# Analog_Switch_Arrays.net
KiCad netlist of a schematic drawn in Altium Designer
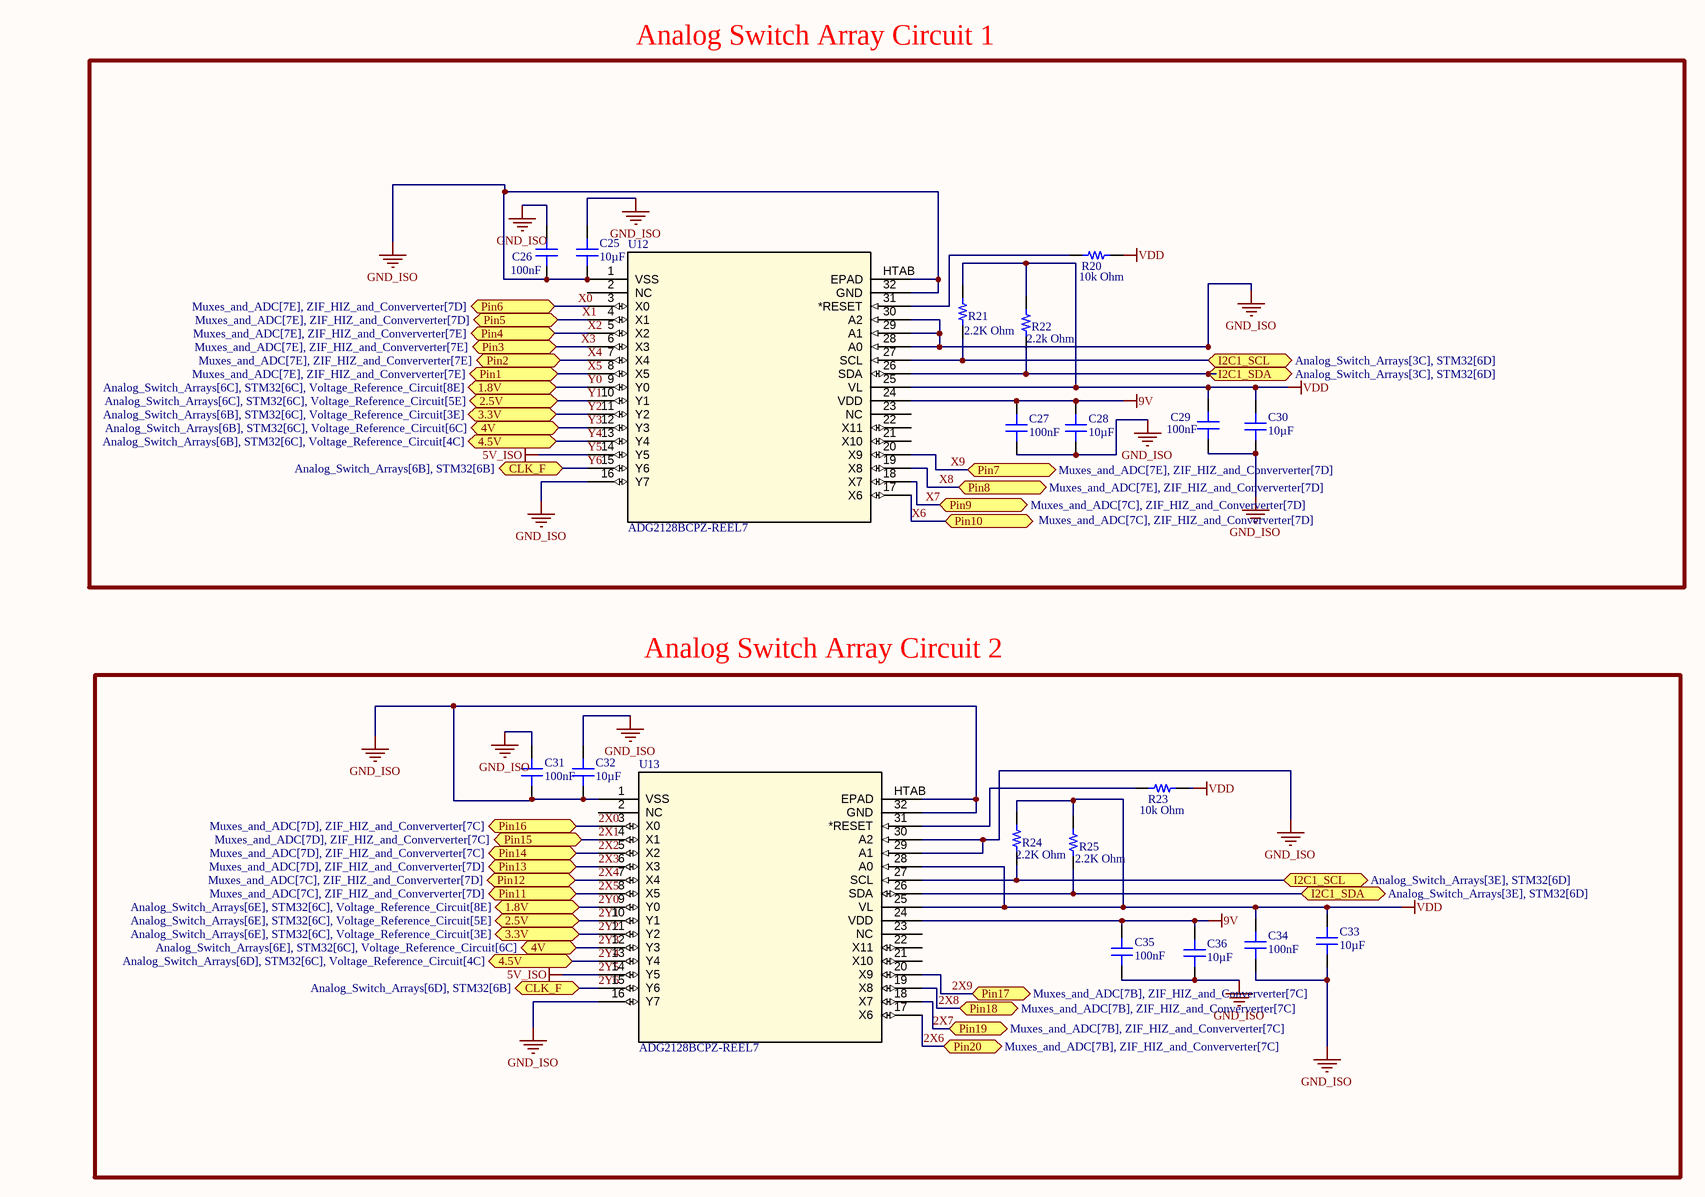
[diagram p0: Analog_Switch_Arrays.SchDoc]

(export (version "E")
  (design (tool "Eeschema 10.0.6"))
  (components
    (comp (ref "C25")
      (value "10µF")
      (footprint "MURATA CAP GCM31M 1206_3216")
      (description "CAP CER 10UF 35V X8M 1206")
      (fields (field (name "PART NUMBER") "GCM31CM8EG106KE08L"))
      (libsource (lib "University of Massachusetts Lowell") (part "CAPACITOR"))
    )
    (comp (ref "C26")
      (value "100nF")
      (footprint "CAP 1206_3216 - 0.8MM")
      (description "CAP CER 1206 0.1F 16V ULTRA STAB")
      (fields (field (name "PART NUMBER") "C1206X104G4HAC7800"))
      (libsource (lib "University of Massachusetts Lowell") (part "CAPACITOR"))
    )
    (comp (ref "C27")
      (value "100nF")
      (footprint "CAP 1206_3216 - 0.8MM")
      (description "CAP CER 1206 0.1F 16V ULTRA STAB")
      (fields (field (name "PART NUMBER") "C1206X104G4HAC7800"))
      (libsource (lib "University of Massachusetts Lowell") (part "CAPACITOR"))
    )
    (comp (ref "C28")
      (value "10µF")
      (footprint "MURATA CAP GCM31M 1206_3216")
      (description "CAP CER 10UF 35V X8M 1206")
      (fields (field (name "PART NUMBER") "GCM31CM8EG106KE08L"))
      (libsource (lib "University of Massachusetts Lowell") (part "CAPACITOR"))
    )
    (comp (ref "C29")
      (value "100nF")
      (footprint "CAP 1206_3216 - 0.8MM")
      (description "CAP CER 1206 0.1F 16V ULTRA STAB")
      (fields (field (name "PART NUMBER") "C1206X104G4HAC7800"))
      (libsource (lib "University of Massachusetts Lowell") (part "CAPACITOR"))
    )
    (comp (ref "C30")
      (value "10µF")
      (footprint "MURATA CAP GCM31M 1206_3216")
      (description "CAP CER 10UF 35V X8M 1206")
      (fields (field (name "PART NUMBER") "GCM31CM8EG106KE08L"))
      (libsource (lib "University of Massachusetts Lowell") (part "CAPACITOR"))
    )
    (comp (ref "C31")
      (value "100nF")
      (footprint "CAP 1206_3216 - 0.8MM")
      (description "CAP CER 1206 0.1F 16V ULTRA STAB")
      (fields (field (name "PART NUMBER") "C1206X104G4HAC7800"))
      (libsource (lib "University of Massachusetts Lowell") (part "CAPACITOR"))
    )
    (comp (ref "C32")
      (value "10µF")
      (footprint "MURATA CAP GCM31M 1206_3216")
      (description "CAP CER 10UF 35V X8M 1206")
      (fields (field (name "PART NUMBER") "GCM31CM8EG106KE08L"))
      (libsource (lib "University of Massachusetts Lowell") (part "CAPACITOR"))
    )
    (comp (ref "C33")
      (value "10µF")
      (footprint "MURATA CAP GCM31M 1206_3216")
      (description "CAP CER 10UF 35V X8M 1206")
      (fields (field (name "PART NUMBER") "GCM31CM8EG106KE08L"))
      (libsource (lib "University of Massachusetts Lowell") (part "CAPACITOR"))
    )
    (comp (ref "C34")
      (value "100nF")
      (footprint "CAP 1206_3216 - 0.8MM")
      (description "CAP CER 1206 0.1F 16V ULTRA STAB")
      (fields (field (name "PART NUMBER") "C1206X104G4HAC7800"))
      (libsource (lib "University of Massachusetts Lowell") (part "CAPACITOR"))
    )
    (comp (ref "C35")
      (value "100nF")
      (footprint "CAP 1206_3216 - 0.8MM")
      (description "CAP CER 1206 0.1F 16V ULTRA STAB")
      (fields (field (name "PART NUMBER") "C1206X104G4HAC7800"))
      (libsource (lib "University of Massachusetts Lowell") (part "CAPACITOR"))
    )
    (comp (ref "C36")
      (value "10µF")
      (footprint "MURATA CAP GCM31M 1206_3216")
      (description "CAP CER 10UF 35V X8M 1206")
      (fields (field (name "PART NUMBER") "GCM31CM8EG106KE08L"))
      (libsource (lib "University of Massachusetts Lowell") (part "CAPACITOR"))
    )
    (comp (ref "R20")
      (value "10k Ohm")
      (footprint "YAGEO RES 1206_3216")
      (description "RES 10K OHM 0.1% 1/4W 1206")
      (fields (field (name "PART NUMBER") "RP1206BRD0710KL"))
      (libsource (lib "University of Massachusetts Lowell") (part "RESISTOR"))
    )
    (comp (ref "R21")
      (value "2.2K Ohm")
      (footprint "RES 1210_3225")
      (description "RES 2.2K OHM 10% 1/2W 1210")
      (fields (field (name "PART NUMBER") "SG732ETTD222K"))
      (libsource (lib "University of Massachusetts Lowell") (part "RESISTOR"))
    )
    (comp (ref "R22")
      (value "2.2k Ohm")
      (footprint "RES 1210_3225")
      (description "RES 2.2K OHM 10% 1/2W 1210")
      (fields (field (name "PART NUMBER") "SG732ETTD222K"))
      (libsource (lib "University of Massachusetts Lowell") (part "RESISTOR"))
    )
    (comp (ref "R23")
      (value "10k Ohm")
      (footprint "YAGEO RES 1206_3216")
      (description "RES 10K OHM 0.1% 1/4W 1206")
      (fields (field (name "PART NUMBER") "RP1206BRD0710KL"))
      (libsource (lib "University of Massachusetts Lowell") (part "RESISTOR"))
    )
    (comp (ref "R24")
      (value "2.2K Ohm")
      (footprint "RES 1210_3225")
      (description "RES 2.2K OHM 10% 1/2W 1210")
      (fields (field (name "PART NUMBER") "SG732ETTD222K"))
      (libsource (lib "University of Massachusetts Lowell") (part "RESISTOR"))
    )
    (comp (ref "R25")
      (value "2.2K Ohm")
      (footprint "RES 1210_3225")
      (description "RES 2.2K OHM 10% 1/2W 1210")
      (fields (field (name "PART NUMBER") "SG732ETTD222K"))
      (libsource (lib "University of Massachusetts Lowell") (part "RESISTOR"))
    )
    (comp (ref "U12")
      (value "ADG2128BCPZ-REEL7")
      (footprint "CP_32_7_ADI")
      (description "I2C CMOS 8 X 12 Analog Switch Array with Dual/Single Supplies")
      (fields (field (name "COPYRIGHT") "Copyright (C) 2025 Ultra Librarian. All rights reserved."))
      (libsource (lib "University of Massachusetts Lowell") (part "ADG2128BCPZ-REEL7"))
    )
    (comp (ref "U13")
      (value "ADG2128BCPZ-REEL7")
      (footprint "CP_32_7_ADI")
      (description "I2C CMOS 8 X 12 Analog Switch Array with Dual/Single Supplies")
      (fields (field (name "COPYRIGHT") "Copyright (C) 2025 Ultra Librarian. All rights reserved."))
      (libsource (lib "University of Massachusetts Lowell") (part "ADG2128BCPZ-REEL7"))
    )
  )
  (nets
    (net (code "1") (name "/2X0") (class "Default")
      (node (ref "U13") (pin "3") (pinfunction "X0_3") (pintype "bidirectional"))
    )
    (net (code "2") (name "/2X1") (class "Default")
      (node (ref "U13") (pin "4") (pinfunction "X1_4") (pintype "bidirectional"))
    )
    (net (code "3") (name "/2X2") (class "Default")
      (node (ref "U13") (pin "5") (pinfunction "X2_5") (pintype "bidirectional"))
    )
    (net (code "4") (name "/2X3") (class "Default")
      (node (ref "U13") (pin "6") (pinfunction "X3_6") (pintype "bidirectional"))
    )
    (net (code "5") (name "/2X4") (class "Default")
      (node (ref "U13") (pin "7") (pinfunction "X4_7") (pintype "bidirectional"))
    )
    (net (code "6") (name "/2X5") (class "Default")
      (node (ref "U13") (pin "8") (pinfunction "X5_8") (pintype "bidirectional"))
    )
    (net (code "7") (name "/2X6") (class "Default")
      (node (ref "U13") (pin "17") (pinfunction "X6_17") (pintype "bidirectional"))
    )
    (net (code "8") (name "/2X7") (class "Default")
      (node (ref "U13") (pin "18") (pinfunction "X7_18") (pintype "bidirectional"))
    )
    (net (code "9") (name "/2X8") (class "Default")
      (node (ref "U13") (pin "19") (pinfunction "X8_19") (pintype "bidirectional"))
    )
    (net (code "10") (name "/2X9") (class "Default")
      (node (ref "U13") (pin "20") (pinfunction "X9_20") (pintype "bidirectional"))
    )
    (net (code "11") (name "/2Y0") (class "Default")
      (node (ref "U12") (pin "9") (pinfunction "Y0_9") (pintype "bidirectional"))
      (node (ref "U13") (pin "9") (pinfunction "Y0_9") (pintype "bidirectional"))
    )
    (net (code "12") (name "/2Y1") (class "Default")
      (node (ref "U12") (pin "10") (pinfunction "Y1_10") (pintype "bidirectional"))
      (node (ref "U13") (pin "10") (pinfunction "Y1_10") (pintype "bidirectional"))
    )
    (net (code "13") (name "/2Y2") (class "Default")
      (node (ref "U12") (pin "11") (pinfunction "Y2_11") (pintype "bidirectional"))
      (node (ref "U13") (pin "11") (pinfunction "Y2_11") (pintype "bidirectional"))
    )
    (net (code "14") (name "/2Y3") (class "Default")
      (node (ref "U12") (pin "12") (pinfunction "Y3_12") (pintype "bidirectional"))
      (node (ref "U13") (pin "12") (pinfunction "Y3_12") (pintype "bidirectional"))
    )
    (net (code "15") (name "/2Y4") (class "Default")
      (node (ref "U12") (pin "13") (pinfunction "Y4_13") (pintype "bidirectional"))
      (node (ref "U13") (pin "13") (pinfunction "Y4_13") (pintype "bidirectional"))
    )
    (net (code "16") (name "/2Y6") (class "Default")
      (node (ref "U12") (pin "15") (pinfunction "Y6_15") (pintype "bidirectional"))
      (node (ref "U13") (pin "15") (pinfunction "Y6_15") (pintype "bidirectional"))
    )
    (net (code "17") (name "/I2C1_SCL") (class "Default")
      (node (ref "R21") (pin "1") (pinfunction "1_1") (pintype "passive"))
      (node (ref "R24") (pin "1") (pinfunction "1_1") (pintype "passive"))
      (node (ref "U12") (pin "27") (pinfunction "SCL_27") (pintype "input"))
      (node (ref "U13") (pin "27") (pinfunction "SCL_27") (pintype "input"))
    )
    (net (code "18") (name "/I2C1_SDA") (class "Default")
      (node (ref "R22") (pin "1") (pinfunction "1_1") (pintype "passive"))
      (node (ref "R25") (pin "1") (pinfunction "1_1") (pintype "passive"))
      (node (ref "U12") (pin "26") (pinfunction "SDA_26") (pintype "bidirectional"))
      (node (ref "U13") (pin "26") (pinfunction "SDA_26") (pintype "bidirectional"))
    )
    (net (code "19") (name "/X0") (class "Default")
      (node (ref "U12") (pin "3") (pinfunction "X0_3") (pintype "bidirectional"))
    )
    (net (code "20") (name "/X1") (class "Default")
      (node (ref "U12") (pin "4") (pinfunction "X1_4") (pintype "bidirectional"))
    )
    (net (code "21") (name "/X2") (class "Default")
      (node (ref "U12") (pin "5") (pinfunction "X2_5") (pintype "bidirectional"))
    )
    (net (code "22") (name "/X3") (class "Default")
      (node (ref "U12") (pin "6") (pinfunction "X3_6") (pintype "bidirectional"))
    )
    (net (code "23") (name "/X4") (class "Default")
      (node (ref "U12") (pin "7") (pinfunction "X4_7") (pintype "bidirectional"))
    )
    (net (code "24") (name "/X5") (class "Default")
      (node (ref "U12") (pin "8") (pinfunction "X5_8") (pintype "bidirectional"))
    )
    (net (code "25") (name "/X6") (class "Default")
      (node (ref "U12") (pin "17") (pinfunction "X6_17") (pintype "bidirectional"))
    )
    (net (code "26") (name "/X7") (class "Default")
      (node (ref "U12") (pin "18") (pinfunction "X7_18") (pintype "bidirectional"))
    )
    (net (code "27") (name "/X8") (class "Default")
      (node (ref "U12") (pin "19") (pinfunction "X8_19") (pintype "bidirectional"))
    )
    (net (code "28") (name "/X9") (class "Default")
      (node (ref "U12") (pin "20") (pinfunction "X9_20") (pintype "bidirectional"))
    )
    (net (code "29") (name "5V_ISO") (class "Default")
      (node (ref "U12") (pin "14") (pinfunction "Y5_14") (pintype "bidirectional"))
      (node (ref "U13") (pin "14") (pinfunction "Y5_14") (pintype "bidirectional"))
    )
    (net (code "30") (name "9V") (class "Default")
      (node (ref "C27") (pin "2") (pinfunction "2_2") (pintype "passive"))
      (node (ref "C28") (pin "2") (pinfunction "2_2") (pintype "passive"))
      (node (ref "C35") (pin "2") (pinfunction "2_2") (pintype "passive"))
      (node (ref "C36") (pin "2") (pinfunction "2_2") (pintype "passive"))
      (node (ref "U12") (pin "24") (pinfunction "VDD_24") (pintype "power_in"))
      (node (ref "U13") (pin "24") (pinfunction "VDD_24") (pintype "power_in"))
    )
    (net (code "31") (name "GND_ISO") (class "Default")
      (node (ref "C25") (pin "1") (pinfunction "1_1") (pintype "passive"))
      (node (ref "C25") (pin "2") (pinfunction "2_2") (pintype "passive"))
      (node (ref "C26") (pin "1") (pinfunction "1_1") (pintype "passive"))
      (node (ref "C26") (pin "2") (pinfunction "2_2") (pintype "passive"))
      (node (ref "C27") (pin "1") (pinfunction "1_1") (pintype "passive"))
      (node (ref "C28") (pin "1") (pinfunction "1_1") (pintype "passive"))
      (node (ref "C29") (pin "1") (pinfunction "1_1") (pintype "passive"))
      (node (ref "C30") (pin "1") (pinfunction "1_1") (pintype "passive"))
      (node (ref "C31") (pin "1") (pinfunction "1_1") (pintype "passive"))
      (node (ref "C31") (pin "2") (pinfunction "2_2") (pintype "passive"))
      (node (ref "C32") (pin "1") (pinfunction "1_1") (pintype "passive"))
      (node (ref "C32") (pin "2") (pinfunction "2_2") (pintype "passive"))
      (node (ref "C33") (pin "1") (pinfunction "1_1") (pintype "passive"))
      (node (ref "C34") (pin "1") (pinfunction "1_1") (pintype "passive"))
      (node (ref "C35") (pin "1") (pinfunction "1_1") (pintype "passive"))
      (node (ref "C36") (pin "1") (pinfunction "1_1") (pintype "passive"))
      (node (ref "U12") (pin "1") (pinfunction "VSS_1") (pintype "power_in"))
      (node (ref "U12") (pin "16") (pinfunction "Y7_16") (pintype "bidirectional"))
      (node (ref "U12") (pin "28") (pinfunction "A0_28") (pintype "input"))
      (node (ref "U12") (pin "29") (pinfunction "A1_29") (pintype "input"))
      (node (ref "U12") (pin "30") (pinfunction "A2_30") (pintype "input"))
      (node (ref "U12") (pin "32") (pinfunction "GND_32") (pintype "power_in"))
      (node (ref "U12") (pin "HTAB") (pinfunction "EPAD_HTAB") (pintype "passive"))
      (node (ref "U13") (pin "1") (pinfunction "VSS_1") (pintype "power_in"))
      (node (ref "U13") (pin "16") (pinfunction "Y7_16") (pintype "bidirectional"))
      (node (ref "U13") (pin "29") (pinfunction "A1_29") (pintype "input"))
      (node (ref "U13") (pin "30") (pinfunction "A2_30") (pintype "input"))
      (node (ref "U13") (pin "32") (pinfunction "GND_32") (pintype "power_in"))
      (node (ref "U13") (pin "HTAB") (pinfunction "EPAD_HTAB") (pintype "passive"))
    )
    (net (code "32") (name "Net-(U12-*RESET)") (class "Default")
      (node (ref "R20") (pin "1") (pinfunction "1_1") (pintype "passive"))
      (node (ref "U12") (pin "31") (pinfunction "*RESET_31") (pintype "input"))
    )
    (net (code "33") (name "Net-(U13-*RESET)") (class "Default")
      (node (ref "R23") (pin "1") (pinfunction "1_1") (pintype "passive"))
      (node (ref "U13") (pin "31") (pinfunction "*RESET_31") (pintype "input"))
    )
    (net (code "34") (name "VDD") (class "Default")
      (node (ref "C29") (pin "2") (pinfunction "2_2") (pintype "passive"))
      (node (ref "C30") (pin "2") (pinfunction "2_2") (pintype "passive"))
      (node (ref "C33") (pin "2") (pinfunction "2_2") (pintype "passive"))
      (node (ref "C34") (pin "2") (pinfunction "2_2") (pintype "passive"))
      (node (ref "R20") (pin "2") (pinfunction "2_2") (pintype "passive"))
      (node (ref "R21") (pin "2") (pinfunction "2_2") (pintype "passive"))
      (node (ref "R22") (pin "2") (pinfunction "2_2") (pintype "passive"))
      (node (ref "R23") (pin "2") (pinfunction "2_2") (pintype "passive"))
      (node (ref "R24") (pin "2") (pinfunction "2_2") (pintype "passive"))
      (node (ref "R25") (pin "2") (pinfunction "2_2") (pintype "passive"))
      (node (ref "U12") (pin "25") (pinfunction "VL_25") (pintype "power_in"))
      (node (ref "U13") (pin "25") (pinfunction "VL_25") (pintype "power_in"))
      (node (ref "U13") (pin "28") (pinfunction "A0_28") (pintype "input"))
    )
    (net (code "35") (name "unconnected-(U12-NC-Pad2)") (class "Default")
      (node (ref "U12") (pin "2") (pinfunction "NC_2") (pintype "passive"))
    )
    (net (code "36") (name "unconnected-(U12-NC-Pad23)") (class "Default")
      (node (ref "U12") (pin "23") (pinfunction "NC_23") (pintype "passive"))
    )
    (net (code "37") (name "unconnected-(U12-X10-Pad21)") (class "Default")
      (node (ref "U12") (pin "21") (pinfunction "X10_21") (pintype "bidirectional"))
    )
    (net (code "38") (name "unconnected-(U12-X11-Pad22)") (class "Default")
      (node (ref "U12") (pin "22") (pinfunction "X11_22") (pintype "bidirectional"))
    )
    (net (code "39") (name "unconnected-(U13-NC-Pad2)") (class "Default")
      (node (ref "U13") (pin "2") (pinfunction "NC_2") (pintype "passive"))
    )
    (net (code "40") (name "unconnected-(U13-NC-Pad23)") (class "Default")
      (node (ref "U13") (pin "23") (pinfunction "NC_23") (pintype "passive"))
    )
    (net (code "41") (name "unconnected-(U13-X10-Pad21)") (class "Default")
      (node (ref "U13") (pin "21") (pinfunction "X10_21") (pintype "bidirectional"))
    )
    (net (code "42") (name "unconnected-(U13-X11-Pad22)") (class "Default")
      (node (ref "U13") (pin "22") (pinfunction "X11_22") (pintype "bidirectional"))
    )
  )
)
